# 07_LMS7002M_Power.net
KiCad netlist of a schematic drawn in Altium Designer
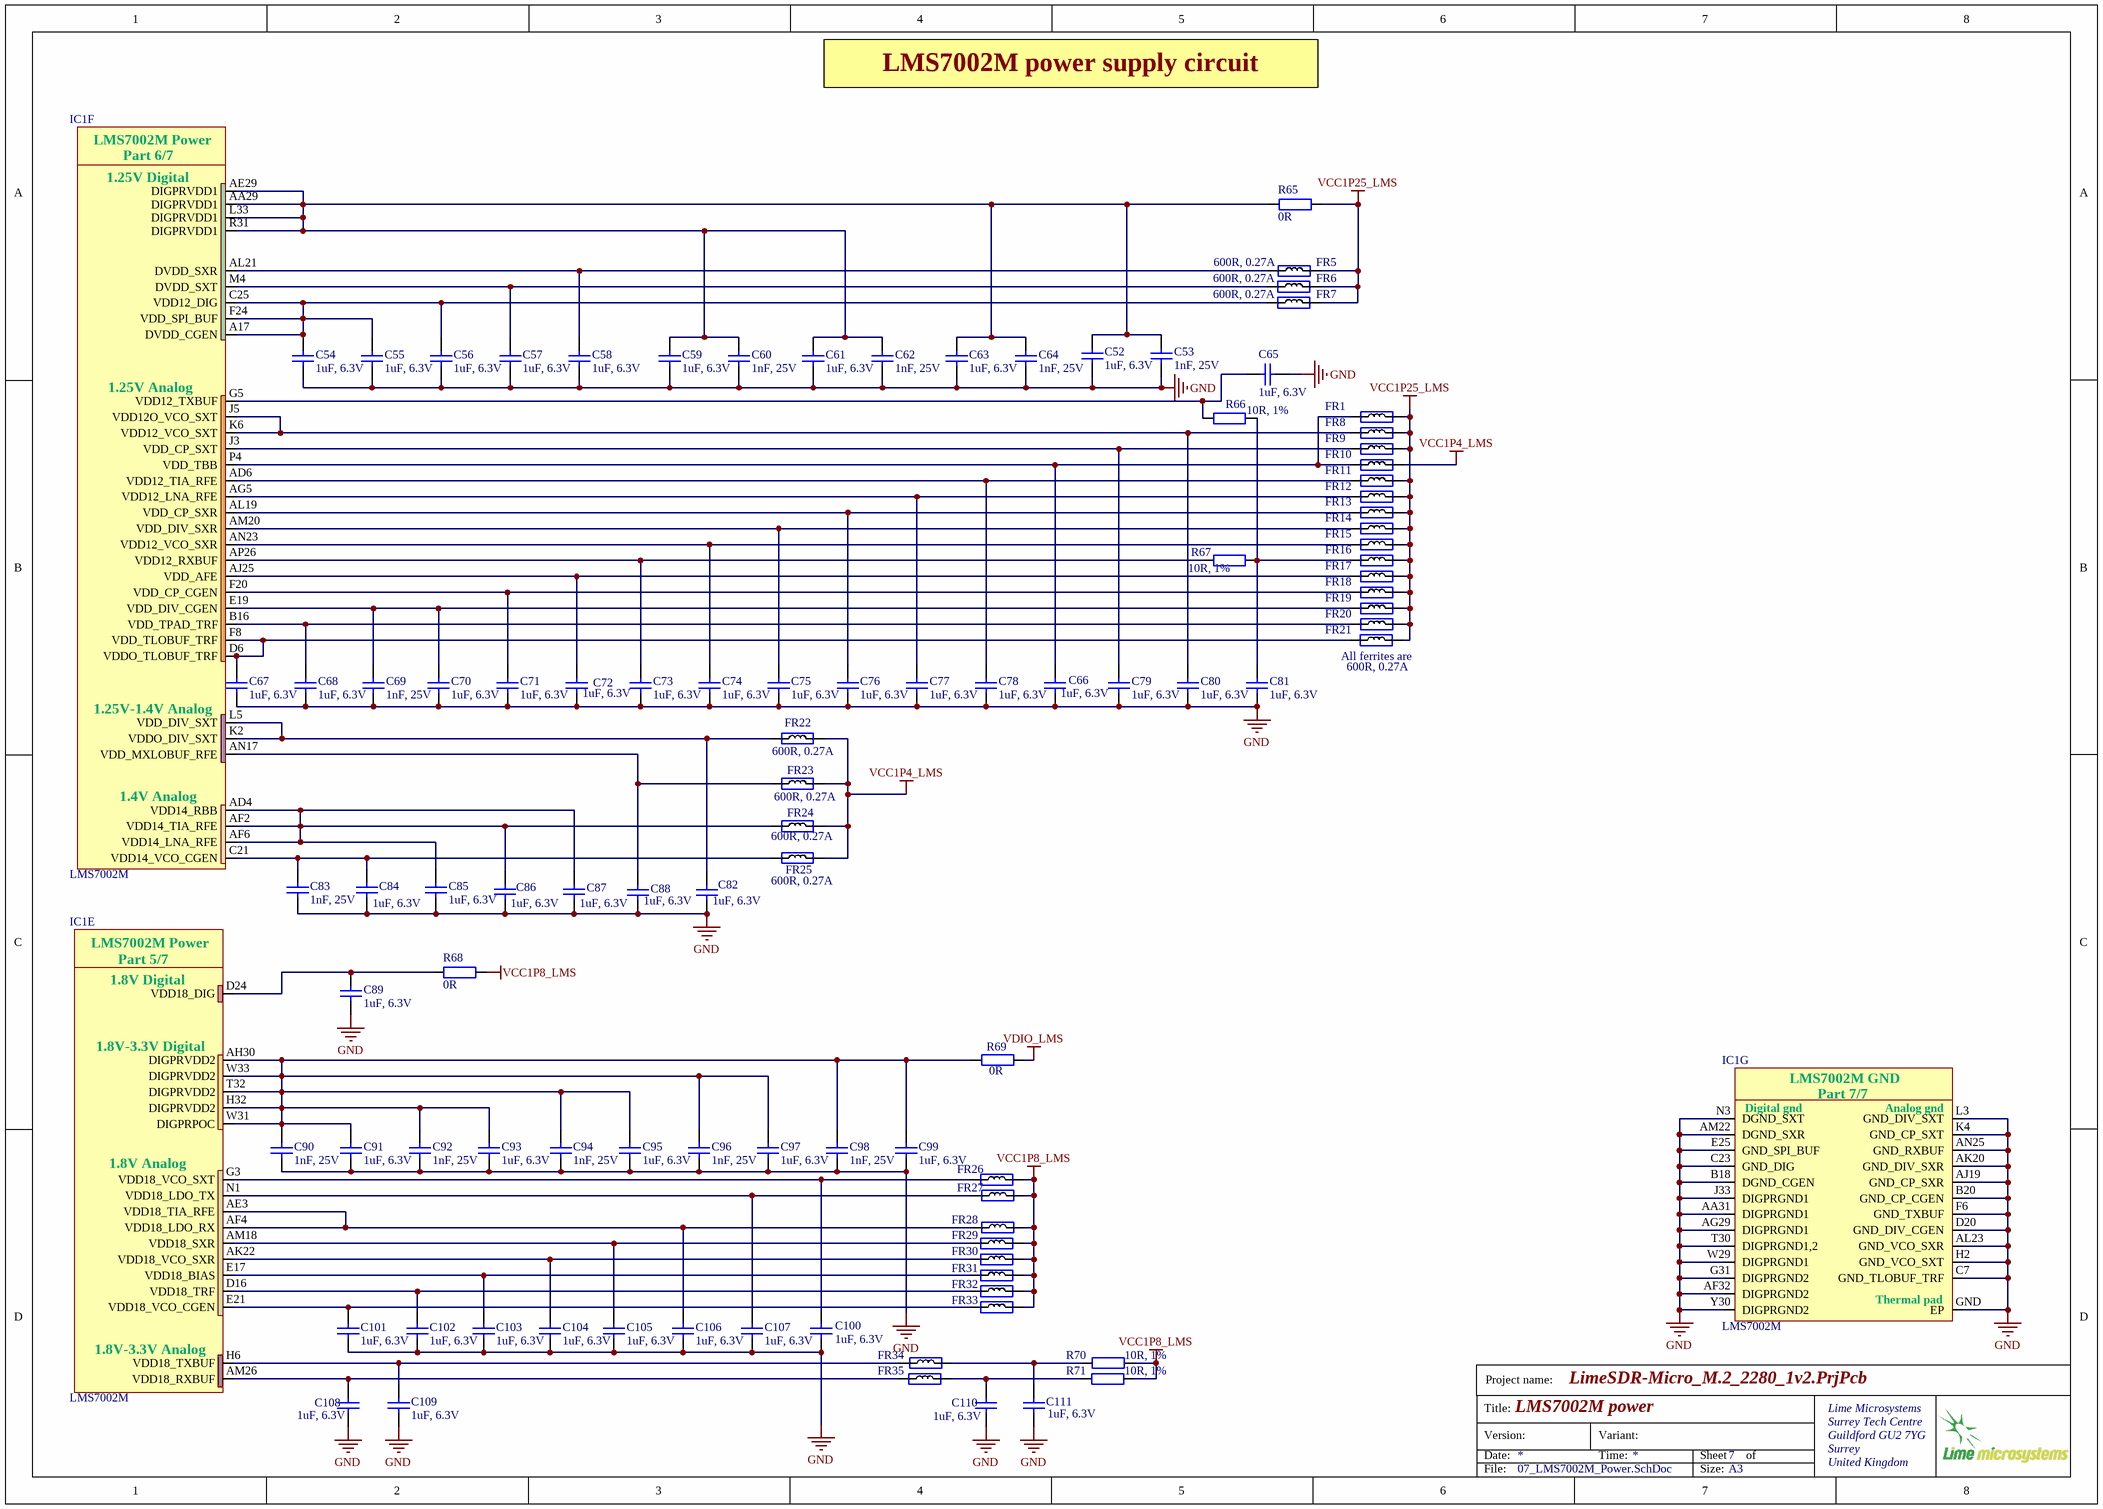
[diagram p0: 07_LMS7002M_Power.SchDoc]

(export (version "E")
  (design (tool "Eeschema 10.0.6"))
  (components
    (comp (ref "C52")
      (value "1uF, 6.3V")
      (footprint "CAP0201")
      (fields (field (name "TOLERANCE") "±20%") (field (name "MANUFACTURER") "TDK Corporation"))
      (libsource (lib "LimeMicroAltiumLib_schLib") (part "Cap_0402"))
    )
    (comp (ref "C53")
      (value "1nF, 25V")
      (footprint "CAP0201")
      (fields (field (name "TOLERANCE") "±10%") (field (name "MANUFACTURER") "TDK Corporation"))
      (libsource (lib "LimeMicroAltiumLib_schLib") (part "Cap_0402"))
    )
    (comp (ref "C54")
      (value "1uF, 6.3V")
      (footprint "CAP0201")
      (fields (field (name "TOLERANCE") "±20%") (field (name "MANUFACTURER") "TDK Corporation"))
      (libsource (lib "LimeMicroAltiumLib_schLib") (part "Cap_0402"))
    )
    (comp (ref "C55")
      (value "1uF, 6.3V")
      (footprint "CAP0201")
      (fields (field (name "TOLERANCE") "±20%") (field (name "MANUFACTURER") "TDK Corporation"))
      (libsource (lib "LimeMicroAltiumLib_schLib") (part "Cap_0402"))
    )
    (comp (ref "C56")
      (value "1uF, 6.3V")
      (footprint "CAP0201")
      (fields (field (name "TOLERANCE") "±20%") (field (name "MANUFACTURER") "TDK Corporation"))
      (libsource (lib "LimeMicroAltiumLib_schLib") (part "Cap_0402"))
    )
    (comp (ref "C57")
      (value "1uF, 6.3V")
      (footprint "CAP0201")
      (fields (field (name "TOLERANCE") "±20%") (field (name "MANUFACTURER") "TDK Corporation"))
      (libsource (lib "LimeMicroAltiumLib_schLib") (part "Cap_0402"))
    )
    (comp (ref "C58")
      (value "1uF, 6.3V")
      (footprint "CAP0201")
      (fields (field (name "TOLERANCE") "±20%") (field (name "MANUFACTURER") "TDK Corporation"))
      (libsource (lib "LimeMicroAltiumLib_schLib") (part "Cap_0402"))
    )
    (comp (ref "C59")
      (value "1uF, 6.3V")
      (footprint "CAP0201")
      (fields (field (name "TOLERANCE") "±20%") (field (name "MANUFACTURER") "TDK Corporation"))
      (libsource (lib "LimeMicroAltiumLib_schLib") (part "Cap_0402"))
    )
    (comp (ref "C60")
      (value "1nF, 25V")
      (footprint "CAP0201")
      (fields (field (name "TOLERANCE") "±10%") (field (name "MANUFACTURER") "TDK Corporation"))
      (libsource (lib "LimeMicroAltiumLib_schLib") (part "Cap_0402"))
    )
    (comp (ref "C61")
      (value "1uF, 6.3V")
      (footprint "CAP0201")
      (fields (field (name "TOLERANCE") "±20%") (field (name "MANUFACTURER") "TDK Corporation"))
      (libsource (lib "LimeMicroAltiumLib_schLib") (part "Cap_0402"))
    )
    (comp (ref "C62")
      (value "1nF, 25V")
      (footprint "CAP0201")
      (fields (field (name "TOLERANCE") "±10%") (field (name "MANUFACTURER") "TDK Corporation"))
      (libsource (lib "LimeMicroAltiumLib_schLib") (part "Cap_0402"))
    )
    (comp (ref "C63")
      (value "1uF, 6.3V")
      (footprint "CAP0201")
      (fields (field (name "TOLERANCE") "±20%") (field (name "MANUFACTURER") "TDK Corporation"))
      (libsource (lib "LimeMicroAltiumLib_schLib") (part "Cap_0402"))
    )
    (comp (ref "C64")
      (value "1nF, 25V")
      (footprint "CAP0201")
      (fields (field (name "TOLERANCE") "±10%") (field (name "MANUFACTURER") "TDK Corporation"))
      (libsource (lib "LimeMicroAltiumLib_schLib") (part "Cap_0402"))
    )
    (comp (ref "C65")
      (value "1uF, 6.3V")
      (footprint "CAP0201")
      (fields (field (name "TOLERANCE") "±20%") (field (name "MANUFACTURER") "TDK Corporation"))
      (libsource (lib "LimeMicroAltiumLib_schLib") (part "Cap_0402"))
    )
    (comp (ref "C66")
      (value "1uF, 6.3V")
      (footprint "CAP0201")
      (fields (field (name "TOLERANCE") "±20%") (field (name "MANUFACTURER") "TDK Corporation"))
      (libsource (lib "LimeMicroAltiumLib_schLib") (part "Cap_0402"))
    )
    (comp (ref "C67")
      (value "1uF, 6.3V")
      (footprint "CAP0201")
      (fields (field (name "TOLERANCE") "±20%") (field (name "MANUFACTURER") "TDK Corporation"))
      (libsource (lib "LimeMicroAltiumLib_schLib") (part "Cap_0402"))
    )
    (comp (ref "C68")
      (value "1uF, 6.3V")
      (footprint "CAP0201")
      (fields (field (name "TOLERANCE") "±20%") (field (name "MANUFACTURER") "TDK Corporation"))
      (libsource (lib "LimeMicroAltiumLib_schLib") (part "Cap_0402"))
    )
    (comp (ref "C69")
      (value "1nF, 25V")
      (footprint "CAP0201")
      (fields (field (name "TOLERANCE") "±10%") (field (name "MANUFACTURER") "TDK Corporation"))
      (libsource (lib "LimeMicroAltiumLib_schLib") (part "Cap_0402"))
    )
    (comp (ref "C70")
      (value "1uF, 6.3V")
      (footprint "CAP0201")
      (fields (field (name "TOLERANCE") "±20%") (field (name "MANUFACTURER") "TDK Corporation"))
      (libsource (lib "LimeMicroAltiumLib_schLib") (part "Cap_0402"))
    )
    (comp (ref "C71")
      (value "1uF, 6.3V")
      (footprint "CAP0201")
      (fields (field (name "TOLERANCE") "±20%") (field (name "MANUFACTURER") "TDK Corporation"))
      (libsource (lib "LimeMicroAltiumLib_schLib") (part "Cap_0402"))
    )
    (comp (ref "C72")
      (value "1uF, 6.3V")
      (footprint "CAP0201")
      (fields (field (name "TOLERANCE") "±20%") (field (name "MANUFACTURER") "TDK Corporation"))
      (libsource (lib "LimeMicroAltiumLib_schLib") (part "Cap_0402"))
    )
    (comp (ref "C73")
      (value "1uF, 6.3V")
      (footprint "CAP0201")
      (fields (field (name "TOLERANCE") "±20%") (field (name "MANUFACTURER") "TDK Corporation"))
      (libsource (lib "LimeMicroAltiumLib_schLib") (part "Cap_0402"))
    )
    (comp (ref "C74")
      (value "1uF, 6.3V")
      (footprint "CAP0201")
      (fields (field (name "TOLERANCE") "±20%") (field (name "MANUFACTURER") "TDK Corporation"))
      (libsource (lib "LimeMicroAltiumLib_schLib") (part "Cap_0402"))
    )
    (comp (ref "C75")
      (value "1uF, 6.3V")
      (footprint "CAP0201")
      (fields (field (name "TOLERANCE") "±20%") (field (name "MANUFACTURER") "TDK Corporation"))
      (libsource (lib "LimeMicroAltiumLib_schLib") (part "Cap_0402"))
    )
    (comp (ref "C76")
      (value "1uF, 6.3V")
      (footprint "CAP0201")
      (fields (field (name "TOLERANCE") "±20%") (field (name "MANUFACTURER") "TDK Corporation"))
      (libsource (lib "LimeMicroAltiumLib_schLib") (part "Cap_0402"))
    )
    (comp (ref "C77")
      (value "1uF, 6.3V")
      (footprint "CAP0201")
      (fields (field (name "TOLERANCE") "±20%") (field (name "MANUFACTURER") "TDK Corporation"))
      (libsource (lib "LimeMicroAltiumLib_schLib") (part "Cap_0402"))
    )
    (comp (ref "C78")
      (value "1uF, 6.3V")
      (footprint "CAP0201")
      (fields (field (name "TOLERANCE") "±20%") (field (name "MANUFACTURER") "TDK Corporation"))
      (libsource (lib "LimeMicroAltiumLib_schLib") (part "Cap_0402"))
    )
    (comp (ref "C79")
      (value "1uF, 6.3V")
      (footprint "CAP0201")
      (fields (field (name "TOLERANCE") "±20%") (field (name "MANUFACTURER") "TDK Corporation"))
      (libsource (lib "LimeMicroAltiumLib_schLib") (part "Cap_0402"))
    )
    (comp (ref "C80")
      (value "1uF, 6.3V")
      (footprint "CAP0201")
      (fields (field (name "TOLERANCE") "±20%") (field (name "MANUFACTURER") "TDK Corporation"))
      (libsource (lib "LimeMicroAltiumLib_schLib") (part "Cap_0402"))
    )
    (comp (ref "C81")
      (value "1uF, 6.3V")
      (footprint "CAP0201")
      (fields (field (name "TOLERANCE") "±20%") (field (name "MANUFACTURER") "TDK Corporation"))
      (libsource (lib "LimeMicroAltiumLib_schLib") (part "Cap_0402"))
    )
    (comp (ref "C82")
      (value "1uF, 6.3V")
      (footprint "CAP0201")
      (fields (field (name "TOLERANCE") "±20%") (field (name "MANUFACTURER") "TDK Corporation"))
      (libsource (lib "LimeMicroAltiumLib_schLib") (part "Cap_0402"))
    )
    (comp (ref "C83")
      (value "1nF, 25V")
      (footprint "CAP0201")
      (fields (field (name "TOLERANCE") "±10%") (field (name "MANUFACTURER") "TDK Corporation"))
      (libsource (lib "LimeMicroAltiumLib_schLib") (part "Cap_0402"))
    )
    (comp (ref "C84")
      (value "1uF, 6.3V")
      (footprint "CAP0201")
      (fields (field (name "TOLERANCE") "±20%") (field (name "MANUFACTURER") "TDK Corporation"))
      (libsource (lib "LimeMicroAltiumLib_schLib") (part "Cap_0402"))
    )
    (comp (ref "C85")
      (value "1uF, 6.3V")
      (footprint "CAP0201")
      (fields (field (name "TOLERANCE") "±20%") (field (name "MANUFACTURER") "TDK Corporation"))
      (libsource (lib "LimeMicroAltiumLib_schLib") (part "Cap_0402"))
    )
    (comp (ref "C86")
      (value "1uF, 6.3V")
      (footprint "CAP0201")
      (fields (field (name "TOLERANCE") "±20%") (field (name "MANUFACTURER") "TDK Corporation"))
      (libsource (lib "LimeMicroAltiumLib_schLib") (part "Cap_0402"))
    )
    (comp (ref "C87")
      (value "1uF, 6.3V")
      (footprint "CAP0201")
      (fields (field (name "TOLERANCE") "±20%") (field (name "MANUFACTURER") "TDK Corporation"))
      (libsource (lib "LimeMicroAltiumLib_schLib") (part "Cap_0402"))
    )
    (comp (ref "C88")
      (value "1uF, 6.3V")
      (footprint "CAP0201")
      (fields (field (name "TOLERANCE") "±20%") (field (name "MANUFACTURER") "TDK Corporation"))
      (libsource (lib "LimeMicroAltiumLib_schLib") (part "Cap_0402"))
    )
    (comp (ref "C89")
      (value "1uF, 6.3V")
      (footprint "CAP0201")
      (fields (field (name "TOLERANCE") "±20%") (field (name "MANUFACTURER") "TDK Corporation"))
      (libsource (lib "LimeMicroAltiumLib_schLib") (part "Cap_0402"))
    )
    (comp (ref "C90")
      (value "1nF, 25V")
      (footprint "CAP0201")
      (fields (field (name "TOLERANCE") "±10%") (field (name "MANUFACTURER") "TDK Corporation"))
      (libsource (lib "LimeMicroAltiumLib_schLib") (part "Cap_0402"))
    )
    (comp (ref "C91")
      (value "1uF, 6.3V")
      (footprint "CAP0201")
      (fields (field (name "TOLERANCE") "±20%") (field (name "MANUFACTURER") "TDK Corporation"))
      (libsource (lib "LimeMicroAltiumLib_schLib") (part "Cap_0402"))
    )
    (comp (ref "C92")
      (value "1nF, 25V")
      (footprint "CAP0201")
      (fields (field (name "TOLERANCE") "±10%") (field (name "MANUFACTURER") "TDK Corporation"))
      (libsource (lib "LimeMicroAltiumLib_schLib") (part "Cap_0402"))
    )
    (comp (ref "C93")
      (value "1uF, 6.3V")
      (footprint "CAP0201")
      (fields (field (name "TOLERANCE") "±20%") (field (name "MANUFACTURER") "TDK Corporation"))
      (libsource (lib "LimeMicroAltiumLib_schLib") (part "Cap_0402"))
    )
    (comp (ref "C94")
      (value "1nF, 25V")
      (footprint "CAP0201")
      (fields (field (name "TOLERANCE") "±10%") (field (name "MANUFACTURER") "TDK Corporation"))
      (libsource (lib "LimeMicroAltiumLib_schLib") (part "Cap_0402"))
    )
    (comp (ref "C95")
      (value "1uF, 6.3V")
      (footprint "CAP0201")
      (fields (field (name "TOLERANCE") "±20%") (field (name "MANUFACTURER") "TDK Corporation"))
      (libsource (lib "LimeMicroAltiumLib_schLib") (part "Cap_0402"))
    )
    (comp (ref "C96")
      (value "1nF, 25V")
      (footprint "CAP0201")
      (fields (field (name "TOLERANCE") "±10%") (field (name "MANUFACTURER") "TDK Corporation"))
      (libsource (lib "LimeMicroAltiumLib_schLib") (part "Cap_0402"))
    )
    (comp (ref "C97")
      (value "1uF, 6.3V")
      (footprint "CAP0201")
      (fields (field (name "TOLERANCE") "±20%") (field (name "MANUFACTURER") "TDK Corporation"))
      (libsource (lib "LimeMicroAltiumLib_schLib") (part "Cap_0402"))
    )
    (comp (ref "C98")
      (value "1nF, 25V")
      (footprint "CAP0201")
      (fields (field (name "TOLERANCE") "±10%") (field (name "MANUFACTURER") "TDK Corporation"))
      (libsource (lib "LimeMicroAltiumLib_schLib") (part "Cap_0402"))
    )
    (comp (ref "C99")
      (value "1uF, 6.3V")
      (footprint "CAP0201")
      (fields (field (name "TOLERANCE") "±20%") (field (name "MANUFACTURER") "TDK Corporation"))
      (libsource (lib "LimeMicroAltiumLib_schLib") (part "Cap_0402"))
    )
    (comp (ref "C100")
      (value "1uF, 6.3V")
      (footprint "CAP0201")
      (fields (field (name "TOLERANCE") "±20%") (field (name "MANUFACTURER") "TDK Corporation"))
      (libsource (lib "LimeMicroAltiumLib_schLib") (part "Cap_0402"))
    )
    (comp (ref "C101")
      (value "1uF, 6.3V")
      (footprint "CAP0201")
      (fields (field (name "TOLERANCE") "±20%") (field (name "MANUFACTURER") "TDK Corporation"))
      (libsource (lib "LimeMicroAltiumLib_schLib") (part "Cap_0402"))
    )
    (comp (ref "C102")
      (value "1uF, 6.3V")
      (footprint "CAP0201")
      (fields (field (name "TOLERANCE") "±20%") (field (name "MANUFACTURER") "TDK Corporation"))
      (libsource (lib "LimeMicroAltiumLib_schLib") (part "Cap_0402"))
    )
    (comp (ref "C103")
      (value "1uF, 6.3V")
      (footprint "CAP0201")
      (fields (field (name "TOLERANCE") "±20%") (field (name "MANUFACTURER") "TDK Corporation"))
      (libsource (lib "LimeMicroAltiumLib_schLib") (part "Cap_0402"))
    )
    (comp (ref "C104")
      (value "1uF, 6.3V")
      (footprint "CAP0201")
      (fields (field (name "TOLERANCE") "±20%") (field (name "MANUFACTURER") "TDK Corporation"))
      (libsource (lib "LimeMicroAltiumLib_schLib") (part "Cap_0402"))
    )
    (comp (ref "C105")
      (value "1uF, 6.3V")
      (footprint "CAP0201")
      (fields (field (name "TOLERANCE") "±20%") (field (name "MANUFACTURER") "TDK Corporation"))
      (libsource (lib "LimeMicroAltiumLib_schLib") (part "Cap_0402"))
    )
    (comp (ref "C106")
      (value "1uF, 6.3V")
      (footprint "CAP0201")
      (fields (field (name "TOLERANCE") "±20%") (field (name "MANUFACTURER") "TDK Corporation"))
      (libsource (lib "LimeMicroAltiumLib_schLib") (part "Cap_0402"))
    )
    (comp (ref "C107")
      (value "1uF, 6.3V")
      (footprint "CAP0201")
      (fields (field (name "TOLERANCE") "±20%") (field (name "MANUFACTURER") "TDK Corporation"))
      (libsource (lib "LimeMicroAltiumLib_schLib") (part "Cap_0402"))
    )
    (comp (ref "C108")
      (value "1uF, 6.3V")
      (footprint "CAP0201")
      (fields (field (name "TOLERANCE") "±20%") (field (name "MANUFACTURER") "TDK Corporation"))
      (libsource (lib "LimeMicroAltiumLib_schLib") (part "Cap_0402"))
    )
    (comp (ref "C109")
      (value "1uF, 6.3V")
      (footprint "CAP0201")
      (fields (field (name "TOLERANCE") "±20%") (field (name "MANUFACTURER") "TDK Corporation"))
      (libsource (lib "LimeMicroAltiumLib_schLib") (part "Cap_0402"))
    )
    (comp (ref "C110")
      (value "1uF, 6.3V")
      (footprint "CAP0201")
      (fields (field (name "TOLERANCE") "±20%") (field (name "MANUFACTURER") "TDK Corporation"))
      (libsource (lib "LimeMicroAltiumLib_schLib") (part "Cap_0402"))
    )
    (comp (ref "C111")
      (value "1uF, 6.3V")
      (footprint "CAP0201")
      (fields (field (name "TOLERANCE") "±20%") (field (name "MANUFACTURER") "TDK Corporation"))
      (libsource (lib "LimeMicroAltiumLib_schLib") (part "Cap_0402"))
    )
    (comp (ref "FR1")
      (value "600R, 0.27A")
      (footprint "RES0201")
      (fields (field (name "MANUFACTURER") "Taiyo Yuden"))
      (libsource (lib "LimeMicroAltiumLib_schLib") (part "Ferrite"))
    )
    (comp (ref "FR5")
      (value "600R, 0.27A")
      (footprint "RES0201")
      (fields (field (name "MANUFACTURER") "Taiyo Yuden"))
      (libsource (lib "LimeMicroAltiumLib_schLib") (part "Ferrite"))
    )
    (comp (ref "FR6")
      (value "600R, 0.27A")
      (footprint "RES0201")
      (fields (field (name "MANUFACTURER") "Taiyo Yuden"))
      (libsource (lib "LimeMicroAltiumLib_schLib") (part "Ferrite"))
    )
    (comp (ref "FR7")
      (value "600R, 0.27A")
      (footprint "RES0201")
      (fields (field (name "MANUFACTURER") "Taiyo Yuden"))
      (libsource (lib "LimeMicroAltiumLib_schLib") (part "Ferrite"))
    )
    (comp (ref "FR8")
      (value "600R, 0.27A")
      (footprint "RES0201")
      (fields (field (name "MANUFACTURER") "Taiyo Yuden"))
      (libsource (lib "LimeMicroAltiumLib_schLib") (part "Ferrite"))
    )
    (comp (ref "FR9")
      (value "600R, 0.27A")
      (footprint "RES0201")
      (fields (field (name "MANUFACTURER") "Taiyo Yuden"))
      (libsource (lib "LimeMicroAltiumLib_schLib") (part "Ferrite"))
    )
    (comp (ref "FR10")
      (value "600R, 0.27A")
      (footprint "RES0201")
      (fields (field (name "MANUFACTURER") "Taiyo Yuden"))
      (libsource (lib "LimeMicroAltiumLib_schLib") (part "Ferrite"))
    )
    (comp (ref "FR11")
      (value "600R, 0.27A")
      (footprint "RES0201")
      (fields (field (name "MANUFACTURER") "Taiyo Yuden"))
      (libsource (lib "LimeMicroAltiumLib_schLib") (part "Ferrite"))
    )
    (comp (ref "FR12")
      (value "600R, 0.27A")
      (footprint "RES0201")
      (fields (field (name "MANUFACTURER") "Taiyo Yuden"))
      (libsource (lib "LimeMicroAltiumLib_schLib") (part "Ferrite"))
    )
    (comp (ref "FR13")
      (value "600R, 0.27A")
      (footprint "RES0201")
      (fields (field (name "MANUFACTURER") "Taiyo Yuden"))
      (libsource (lib "LimeMicroAltiumLib_schLib") (part "Ferrite"))
    )
    (comp (ref "FR14")
      (value "600R, 0.27A")
      (footprint "RES0201")
      (fields (field (name "MANUFACTURER") "Taiyo Yuden"))
      (libsource (lib "LimeMicroAltiumLib_schLib") (part "Ferrite"))
    )
    (comp (ref "FR15")
      (value "600R, 0.27A")
      (footprint "RES0201")
      (fields (field (name "MANUFACTURER") "Taiyo Yuden"))
      (libsource (lib "LimeMicroAltiumLib_schLib") (part "Ferrite"))
    )
    (comp (ref "FR16")
      (value "600R, 0.27A")
      (footprint "RES0201")
      (fields (field (name "MANUFACTURER") "Taiyo Yuden"))
      (libsource (lib "LimeMicroAltiumLib_schLib") (part "Ferrite"))
    )
    (comp (ref "FR17")
      (value "600R, 0.27A")
      (footprint "RES0201")
      (fields (field (name "MANUFACTURER") "Taiyo Yuden"))
      (libsource (lib "LimeMicroAltiumLib_schLib") (part "Ferrite"))
    )
    (comp (ref "FR18")
      (value "600R, 0.27A")
      (footprint "RES0201")
      (fields (field (name "MANUFACTURER") "Taiyo Yuden"))
      (libsource (lib "LimeMicroAltiumLib_schLib") (part "Ferrite"))
    )
    (comp (ref "FR19")
      (value "600R, 0.27A")
      (footprint "RES0201")
      (fields (field (name "MANUFACTURER") "Taiyo Yuden"))
      (libsource (lib "LimeMicroAltiumLib_schLib") (part "Ferrite"))
    )
    (comp (ref "FR20")
      (value "600R, 0.27A")
      (footprint "RES0201")
      (fields (field (name "MANUFACTURER") "Taiyo Yuden"))
      (libsource (lib "LimeMicroAltiumLib_schLib") (part "Ferrite"))
    )
    (comp (ref "FR21")
      (value "600R, 0.27A")
      (footprint "RES0201")
      (fields (field (name "MANUFACTURER") "Taiyo Yuden"))
      (libsource (lib "LimeMicroAltiumLib_schLib") (part "Ferrite"))
    )
    (comp (ref "FR22")
      (value "600R, 0.27A")
      (footprint "RES0201")
      (fields (field (name "MANUFACTURER") "Taiyo Yuden"))
      (libsource (lib "LimeMicroAltiumLib_schLib") (part "Ferrite"))
    )
    (comp (ref "FR23")
      (value "600R, 0.27A")
      (footprint "RES0201")
      (fields (field (name "MANUFACTURER") "Taiyo Yuden"))
      (libsource (lib "LimeMicroAltiumLib_schLib") (part "Ferrite"))
    )
    (comp (ref "FR24")
      (value "600R, 0.27A")
      (footprint "RES0201")
      (fields (field (name "MANUFACTURER") "Taiyo Yuden"))
      (libsource (lib "LimeMicroAltiumLib_schLib") (part "Ferrite"))
    )
    (comp (ref "FR25")
      (value "600R, 0.27A")
      (footprint "RES0201")
      (fields (field (name "MANUFACTURER") "Taiyo Yuden"))
      (libsource (lib "LimeMicroAltiumLib_schLib") (part "Ferrite"))
    )
    (comp (ref "FR26")
      (value "600R, 0.27A")
      (footprint "RES0201")
      (fields (field (name "MANUFACTURER") "Taiyo Yuden"))
      (libsource (lib "LimeMicroAltiumLib_schLib") (part "Ferrite"))
    )
    (comp (ref "FR27")
      (value "600R, 0.27A")
      (footprint "RES0201")
      (fields (field (name "MANUFACTURER") "Taiyo Yuden"))
      (libsource (lib "") (part "Ferrite_1"))
    )
    (comp (ref "FR28")
      (value "600R, 0.27A")
      (footprint "RES0201")
      (fields (field (name "MANUFACTURER") "Taiyo Yuden"))
      (libsource (lib "") (part "Ferrite_1"))
    )
    (comp (ref "FR29")
      (value "600R, 0.27A")
      (footprint "RES0201")
      (fields (field (name "MANUFACTURER") "Taiyo Yuden"))
      (libsource (lib "LimeMicroAltiumLib_schLib") (part "Ferrite"))
    )
    (comp (ref "FR30")
      (value "600R, 0.27A")
      (footprint "RES0201")
      (fields (field (name "MANUFACTURER") "Taiyo Yuden"))
      (libsource (lib "LimeMicroAltiumLib_schLib") (part "Ferrite"))
    )
    (comp (ref "FR31")
      (value "600R, 0.27A")
      (footprint "RES0201")
      (fields (field (name "MANUFACTURER") "Taiyo Yuden"))
      (libsource (lib "LimeMicroAltiumLib_schLib") (part "Ferrite"))
    )
    (comp (ref "FR32")
      (value "600R, 0.27A")
      (footprint "RES0201")
      (fields (field (name "MANUFACTURER") "Taiyo Yuden"))
      (libsource (lib "LimeMicroAltiumLib_schLib") (part "Ferrite"))
    )
    (comp (ref "FR33")
      (value "600R, 0.27A")
      (footprint "RES0201")
      (fields (field (name "MANUFACTURER") "Taiyo Yuden"))
      (libsource (lib "LimeMicroAltiumLib_schLib") (part "Ferrite"))
    )
    (comp (ref "FR34")
      (value "600R, 0.27A")
      (footprint "RES0201")
      (fields (field (name "MANUFACTURER") "Taiyo Yuden"))
      (libsource (lib "") (part "Ferrite_1"))
    )
    (comp (ref "FR35")
      (value "600R, 0.27A")
      (footprint "RES0201")
      (fields (field (name "MANUFACTURER") "Taiyo Yuden"))
      (libsource (lib "LimeMicroAltiumLib_schLib") (part "Ferrite"))
    )
    (comp (ref "IC1")
      (value "LMS7002M")
      (footprint "LMS7002M_v5_LESS_SILK")
      (description "Schematic symbol revision 4. Default footprint - 0.31mm pad")
      (fields (field (name "MANUFACTURER") "Lime Microsystems"))
      (libsource (lib "LimeMicroAltiumLib_schLib_r04") (part "LMS7002Mr4"))
    )
    (comp (ref "R65")
      (value "0R")
      (footprint "RES0402")
      (fields (field (name "MANUFACTURER") "Yageo") (field (name "TOLERANCE") "Jumper"))
      (libsource (lib "LimeMicroAltiumLib_schLib") (part "Res_0402"))
    )
    (comp (ref "R66")
      (value "10R, 1%")
      (footprint "RES0201")
      (fields
        (field (name "MANUFACTURER") "Panasonic Electronic Components")
        (field (name "TOLERANCE") "±1%")
      )
      (libsource (lib "LimeMicroAltiumLib_schLib") (part "Res_0402"))
    )
    (comp (ref "R67")
      (value "10R, 1%")
      (footprint "RES0201")
      (fields
        (field (name "MANUFACTURER") "Panasonic Electronic Components")
        (field (name "TOLERANCE") "±1%")
      )
      (libsource (lib "LimeMicroAltiumLib_schLib") (part "Res_0402"))
    )
    (comp (ref "R68")
      (value "0R")
      (footprint "RES0201")
      (fields (field (name "MANUFACTURER") "Yageo") (field (name "TOLERANCE") "5%"))
      (libsource (lib "LimeMicroAltiumLib_schLib") (part "Res_0402"))
    )
    (comp (ref "R69")
      (value "0R")
      (footprint "RES0402")
      (fields (field (name "MANUFACTURER") "Yageo") (field (name "TOLERANCE") "Jumper"))
      (libsource (lib "LimeMicroAltiumLib_schLib") (part "Res_0402"))
    )
    (comp (ref "R70")
      (value "10R, 1%")
      (footprint "RES0201")
      (fields
        (field (name "MANUFACTURER") "Panasonic Electronic Components")
        (field (name "TOLERANCE") "±1%")
      )
      (libsource (lib "LimeMicroAltiumLib_schLib") (part "Res_0402"))
    )
    (comp (ref "R71")
      (value "10R, 1%")
      (footprint "RES0201")
      (fields
        (field (name "MANUFACTURER") "Panasonic Electronic Components")
        (field (name "TOLERANCE") "±1%")
      )
      (libsource (lib "LimeMicroAltiumLib_schLib") (part "Res_0402"))
    )
  )
  (nets
    (net (code "1") (name "GND") (class "Default")
      (node (ref "C100") (pin "2") (pinfunction "2_2") (pintype "passive"))
      (node (ref "C101") (pin "2") (pinfunction "2_2") (pintype "passive"))
      (node (ref "C102") (pin "2") (pinfunction "2_2") (pintype "passive"))
      (node (ref "C103") (pin "2") (pinfunction "2_2") (pintype "passive"))
      (node (ref "C104") (pin "2") (pinfunction "2_2") (pintype "passive"))
      (node (ref "C105") (pin "2") (pinfunction "2_2") (pintype "passive"))
      (node (ref "C106") (pin "2") (pinfunction "2_2") (pintype "passive"))
      (node (ref "C107") (pin "2") (pinfunction "2_2") (pintype "passive"))
      (node (ref "C108") (pin "2") (pinfunction "2_2") (pintype "passive"))
      (node (ref "C109") (pin "2") (pinfunction "2_2") (pintype "passive"))
      (node (ref "C110") (pin "2") (pinfunction "2_2") (pintype "passive"))
      (node (ref "C111") (pin "2") (pinfunction "2_2") (pintype "passive"))
      (node (ref "C52") (pin "2") (pinfunction "2_2") (pintype "passive"))
      (node (ref "C53") (pin "2") (pinfunction "2_2") (pintype "passive"))
      (node (ref "C54") (pin "2") (pinfunction "2_2") (pintype "passive"))
      (node (ref "C55") (pin "2") (pinfunction "2_2") (pintype "passive"))
      (node (ref "C56") (pin "2") (pinfunction "2_2") (pintype "passive"))
      (node (ref "C57") (pin "1") (pinfunction "1_1") (pintype "passive"))
      (node (ref "C58") (pin "2") (pinfunction "2_2") (pintype "passive"))
      (node (ref "C59") (pin "2") (pinfunction "2_2") (pintype "passive"))
      (node (ref "C60") (pin "2") (pinfunction "2_2") (pintype "passive"))
      (node (ref "C61") (pin "2") (pinfunction "2_2") (pintype "passive"))
      (node (ref "C62") (pin "2") (pinfunction "2_2") (pintype "passive"))
      (node (ref "C63") (pin "2") (pinfunction "2_2") (pintype "passive"))
      (node (ref "C64") (pin "2") (pinfunction "2_2") (pintype "passive"))
      (node (ref "C65") (pin "2") (pinfunction "2_2") (pintype "passive"))
      (node (ref "C66") (pin "2") (pinfunction "2_2") (pintype "passive"))
      (node (ref "C67") (pin "2") (pinfunction "2_2") (pintype "passive"))
      (node (ref "C68") (pin "2") (pinfunction "2_2") (pintype "passive"))
      (node (ref "C69") (pin "2") (pinfunction "2_2") (pintype "passive"))
      (node (ref "C70") (pin "2") (pinfunction "2_2") (pintype "passive"))
      (node (ref "C71") (pin "1") (pinfunction "1_1") (pintype "passive"))
      (node (ref "C72") (pin "2") (pinfunction "2_2") (pintype "passive"))
      (node (ref "C73") (pin "2") (pinfunction "2_2") (pintype "passive"))
      (node (ref "C74") (pin "2") (pinfunction "2_2") (pintype "passive"))
      (node (ref "C75") (pin "2") (pinfunction "2_2") (pintype "passive"))
      (node (ref "C76") (pin "2") (pinfunction "2_2") (pintype "passive"))
      (node (ref "C77") (pin "2") (pinfunction "2_2") (pintype "passive"))
      (node (ref "C78") (pin "1") (pinfunction "1_1") (pintype "passive"))
      (node (ref "C79") (pin "2") (pinfunction "2_2") (pintype "passive"))
      (node (ref "C80") (pin "1") (pinfunction "1_1") (pintype "passive"))
      (node (ref "C81") (pin "1") (pinfunction "1_1") (pintype "passive"))
      (node (ref "C82") (pin "2") (pinfunction "2_2") (pintype "passive"))
      (node (ref "C83") (pin "2") (pinfunction "2_2") (pintype "passive"))
      (node (ref "C84") (pin "2") (pinfunction "2_2") (pintype "passive"))
      (node (ref "C85") (pin "2") (pinfunction "2_2") (pintype "passive"))
      (node (ref "C86") (pin "2") (pinfunction "2_2") (pintype "passive"))
      (node (ref "C87") (pin "2") (pinfunction "2_2") (pintype "passive"))
      (node (ref "C88") (pin "2") (pinfunction "2_2") (pintype "passive"))
      (node (ref "C89") (pin "2") (pinfunction "2_2") (pintype "passive"))
      (node (ref "C90") (pin "2") (pinfunction "2_2") (pintype "passive"))
      (node (ref "C91") (pin "2") (pinfunction "2_2") (pintype "passive"))
      (node (ref "C92") (pin "2") (pinfunction "2_2") (pintype "passive"))
      (node (ref "C93") (pin "2") (pinfunction "2_2") (pintype "passive"))
      (node (ref "C94") (pin "2") (pinfunction "2_2") (pintype "passive"))
      (node (ref "C95") (pin "2") (pinfunction "2_2") (pintype "passive"))
      (node (ref "C96") (pin "2") (pinfunction "2_2") (pintype "passive"))
      (node (ref "C97") (pin "2") (pinfunction "2_2") (pintype "passive"))
      (node (ref "C98") (pin "2") (pinfunction "2_2") (pintype "passive"))
      (node (ref "C99") (pin "2") (pinfunction "2_2") (pintype "passive"))
      (node (ref "IC1") (pin "AA31") (pinfunction "DIGPRGND1_AA31") (pintype "passive"))
      (node (ref "IC1") (pin "AF32") (pinfunction "DIGPRGND2_AF32") (pintype "passive"))
      (node (ref "IC1") (pin "AG29") (pinfunction "DIGPRGND1_AG29") (pintype "passive"))
      (node (ref "IC1") (pin "AJ19") (pinfunction "GND_CP_SXR_AJ19") (pintype "passive"))
      (node (ref "IC1") (pin "AK20") (pinfunction "GND_DIV_SXR_AK20") (pintype "passive"))
      (node (ref "IC1") (pin "AL23") (pinfunction "GND_VCO_SXR_AL23") (pintype "passive"))
      (node (ref "IC1") (pin "AM22") (pinfunction "DGND_SXR_AM22") (pintype "passive"))
      (node (ref "IC1") (pin "AN25") (pinfunction "GND_RXBUF_AN25") (pintype "passive"))
      (node (ref "IC1") (pin "B18") (pinfunction "DGND_CGEN_B18") (pintype "passive"))
      (node (ref "IC1") (pin "B20") (pinfunction "GND_CP_CGEN_B20") (pintype "passive"))
      (node (ref "IC1") (pin "C23") (pinfunction "GND_DIG_C23") (pintype "passive"))
      (node (ref "IC1") (pin "C7") (pinfunction "GND_TLOBUF_TRF_C7") (pintype "passive"))
      (node (ref "IC1") (pin "D20") (pinfunction "GND_DIV_CGEN_D20") (pintype "passive"))
      (node (ref "IC1") (pin "E25") (pinfunction "GND_SPI_BUF_E25") (pintype "passive"))
      (node (ref "IC1") (pin "F6") (pinfunction "GND_TXBUF_F6") (pintype "passive"))
      (node (ref "IC1") (pin "G31") (pinfunction "DIGPRGND2_G31") (pintype "passive"))
      (node (ref "IC1") (pin "GND") (pinfunction "EP_GND") (pintype "passive"))
      (node (ref "IC1") (pin "H2") (pinfunction "GND_VCO_SXT_H2") (pintype "passive"))
      (node (ref "IC1") (pin "J33") (pinfunction "DIGPRGND1_J33") (pintype "passive"))
      (node (ref "IC1") (pin "K4") (pinfunction "GND_CP_SXT_K4") (pintype "passive"))
      (node (ref "IC1") (pin "L3") (pinfunction "GND_DIV_SXT_L3") (pintype "passive"))
      (node (ref "IC1") (pin "N3") (pinfunction "DGND_SXT_N3") (pintype "passive"))
      (node (ref "IC1") (pin "T30") (pinfunction "DIGPRGND1,2_T30") (pintype "passive"))
      (node (ref "IC1") (pin "W29") (pinfunction "DIGPRGND1_W29") (pintype "passive"))
      (node (ref "IC1") (pin "Y30") (pinfunction "DIGPRGND2_Y30") (pintype "passive"))
    )
    (net (code "2") (name "Net-(C52-Pad1)") (class "Default")
      (node (ref "C52") (pin "1") (pinfunction "1_1") (pintype "passive"))
      (node (ref "C53") (pin "1") (pinfunction "1_1") (pintype "passive"))
      (node (ref "C59") (pin "1") (pinfunction "1_1") (pintype "passive"))
      (node (ref "C60") (pin "1") (pinfunction "1_1") (pintype "passive"))
      (node (ref "C61") (pin "1") (pinfunction "1_1") (pintype "passive"))
      (node (ref "C62") (pin "1") (pinfunction "1_1") (pintype "passive"))
      (node (ref "C63") (pin "1") (pinfunction "1_1") (pintype "passive"))
      (node (ref "C64") (pin "1") (pinfunction "1_1") (pintype "passive"))
      (node (ref "IC1") (pin "AA29") (pinfunction "DIGPRVDD1_AA29") (pintype "power_in"))
      (node (ref "IC1") (pin "AE29") (pinfunction "DIGPRVDD1_AE29") (pintype "power_in"))
      (node (ref "IC1") (pin "L33") (pinfunction "DIGPRVDD1_L33") (pintype "power_in"))
      (node (ref "IC1") (pin "R31") (pinfunction "DIGPRVDD1_R31") (pintype "power_in"))
      (node (ref "R65") (pin "2") (pinfunction "2_2") (pintype "passive"))
    )
    (net (code "3") (name "Net-(C81-Pad2)") (class "Default")
      (node (ref "C81") (pin "2") (pinfunction "2_2") (pintype "passive"))
      (node (ref "FR16") (pin "1") (pinfunction "1_1") (pintype "passive"))
      (node (ref "R66") (pin "2") (pinfunction "2_2") (pintype "passive"))
      (node (ref "R67") (pin "2") (pinfunction "2_2") (pintype "passive"))
    )
    (net (code "4") (name "Net-(C110-Pad1)") (class "Default")
      (node (ref "C110") (pin "1") (pinfunction "1_1") (pintype "passive"))
      (node (ref "FR35") (pin "2") (pinfunction "2_2") (pintype "passive"))
      (node (ref "R71") (pin "2") (pinfunction "2_2") (pintype "passive"))
    )
    (net (code "5") (name "Net-(C111-Pad1)") (class "Default")
      (node (ref "C111") (pin "1") (pinfunction "1_1") (pintype "passive"))
      (node (ref "FR34") (pin "1") (pinfunction "1_1") (pintype "passive"))
      (node (ref "R70") (pin "1") (pinfunction "1_1") (pintype "passive"))
    )
    (net (code "6") (name "Net-(IC1E-DIGPRPOC)") (class "Default")
      (node (ref "C90") (pin "1") (pinfunction "1_1") (pintype "passive"))
      (node (ref "C91") (pin "1") (pinfunction "1_1") (pintype "passive"))
      (node (ref "C92") (pin "1") (pinfunction "1_1") (pintype "passive"))
      (node (ref "C93") (pin "1") (pinfunction "1_1") (pintype "passive"))
      (node (ref "C94") (pin "1") (pinfunction "1_1") (pintype "passive"))
      (node (ref "C95") (pin "1") (pinfunction "1_1") (pintype "passive"))
      (node (ref "C96") (pin "1") (pinfunction "1_1") (pintype "passive"))
      (node (ref "C97") (pin "1") (pinfunction "1_1") (pintype "passive"))
      (node (ref "C98") (pin "1") (pinfunction "1_1") (pintype "passive"))
      (node (ref "C99") (pin "1") (pinfunction "1_1") (pintype "passive"))
      (node (ref "IC1") (pin "AH30") (pinfunction "DIGPRVDD2_AH30") (pintype "power_in"))
      (node (ref "IC1") (pin "H32") (pinfunction "DIGPRVDD2_H32") (pintype "power_in"))
      (node (ref "IC1") (pin "T32") (pinfunction "DIGPRVDD2_T32") (pintype "power_in"))
      (node (ref "IC1") (pin "W31") (pinfunction "DIGPRPOC_W31") (pintype "power_in"))
      (node (ref "IC1") (pin "W33") (pinfunction "DIGPRVDD2_W33") (pintype "power_in"))
      (node (ref "R69") (pin "2") (pinfunction "2_2") (pintype "passive"))
    )
    (net (code "7") (name "Net-(IC1E-VDD18_BIAS)") (class "Default")
      (node (ref "C103") (pin "1") (pinfunction "1_1") (pintype "passive"))
      (node (ref "FR31") (pin "1") (pinfunction "1_1") (pintype "passive"))
      (node (ref "IC1") (pin "E17") (pinfunction "VDD18_BIAS_E17") (pintype "power_in"))
    )
    (net (code "8") (name "Net-(IC1E-VDD18_DIG)") (class "Default")
      (node (ref "C89") (pin "1") (pinfunction "1_1") (pintype "passive"))
      (node (ref "IC1") (pin "D24") (pinfunction "VDD18_DIG_D24") (pintype "power_in"))
      (node (ref "R68") (pin "1") (pinfunction "1_1") (pintype "passive"))
    )
    (net (code "9") (name "Net-(IC1E-VDD18_LDO_RX)") (class "Default")
      (node (ref "C106") (pin "1") (pinfunction "1_1") (pintype "passive"))
      (node (ref "FR28") (pin "2") (pinfunction "2_2") (pintype "passive"))
      (node (ref "IC1") (pin "AE3") (pinfunction "VDD18_TIA_RFE_AE3") (pintype "power_in"))
      (node (ref "IC1") (pin "AF4") (pinfunction "VDD18_LDO_RX_AF4") (pintype "power_in"))
    )
    (net (code "10") (name "Net-(IC1E-VDD18_LDO_TX)") (class "Default")
      (node (ref "C107") (pin "1") (pinfunction "1_1") (pintype "passive"))
      (node (ref "FR27") (pin "2") (pinfunction "2_2") (pintype "passive"))
      (node (ref "IC1") (pin "N1") (pinfunction "VDD18_LDO_TX_N1") (pintype "power_in"))
    )
    (net (code "11") (name "Net-(IC1E-VDD18_RXBUF)") (class "Default")
      (node (ref "C108") (pin "1") (pinfunction "1_1") (pintype "passive"))
      (node (ref "FR35") (pin "1") (pinfunction "1_1") (pintype "passive"))
      (node (ref "IC1") (pin "AM26") (pinfunction "VDD18_RXBUF_AM26") (pintype "power_in"))
    )
    (net (code "12") (name "Net-(IC1E-VDD18_SXR)") (class "Default")
      (node (ref "C105") (pin "1") (pinfunction "1_1") (pintype "passive"))
      (node (ref "FR29") (pin "1") (pinfunction "1_1") (pintype "passive"))
      (node (ref "IC1") (pin "AM18") (pinfunction "VDD18_SXR_AM18") (pintype "power_in"))
    )
    (net (code "13") (name "Net-(IC1E-VDD18_TRF)") (class "Default")
      (node (ref "C102") (pin "1") (pinfunction "1_1") (pintype "passive"))
      (node (ref "FR32") (pin "1") (pinfunction "1_1") (pintype "passive"))
      (node (ref "IC1") (pin "D16") (pinfunction "VDD18_TRF_D16") (pintype "power_in"))
    )
    (net (code "14") (name "Net-(IC1E-VDD18_TXBUF)") (class "Default")
      (node (ref "C109") (pin "1") (pinfunction "1_1") (pintype "passive"))
      (node (ref "FR34") (pin "2") (pinfunction "2_2") (pintype "passive"))
      (node (ref "IC1") (pin "H6") (pinfunction "VDD18_TXBUF_H6") (pintype "power_in"))
    )
    (net (code "15") (name "Net-(IC1E-VDD18_VCO_CGEN)") (class "Default")
      (node (ref "C101") (pin "1") (pinfunction "1_1") (pintype "passive"))
      (node (ref "FR33") (pin "1") (pinfunction "1_1") (pintype "passive"))
      (node (ref "IC1") (pin "E21") (pinfunction "VDD18_VCO_CGEN_E21") (pintype "power_in"))
    )
    (net (code "16") (name "Net-(IC1E-VDD18_VCO_SXR)") (class "Default")
      (node (ref "C104") (pin "1") (pinfunction "1_1") (pintype "passive"))
      (node (ref "FR30") (pin "1") (pinfunction "1_1") (pintype "passive"))
      (node (ref "IC1") (pin "AK22") (pinfunction "VDD18_VCO_SXR_AK22") (pintype "power_in"))
    )
    (net (code "17") (name "Net-(IC1E-VDD18_VCO_SXT)") (class "Default")
      (node (ref "C100") (pin "1") (pinfunction "1_1") (pintype "passive"))
      (node (ref "FR26") (pin "1") (pinfunction "1_1") (pintype "passive"))
      (node (ref "IC1") (pin "G3") (pinfunction "VDD18_VCO_SXT_G3") (pintype "power_in"))
    )
    (net (code "18") (name "Net-(IC1F-DVDD_CGEN)") (class "Default")
      (node (ref "C54") (pin "1") (pinfunction "1_1") (pintype "passive"))
      (node (ref "C55") (pin "1") (pinfunction "1_1") (pintype "passive"))
      (node (ref "C56") (pin "1") (pinfunction "1_1") (pintype "passive"))
      (node (ref "FR7") (pin "1") (pinfunction "1_1") (pintype "passive"))
      (node (ref "IC1") (pin "A17") (pinfunction "DVDD_CGEN_A17") (pintype "power_in"))
      (node (ref "IC1") (pin "C25") (pinfunction "VDD12_DIG_C25") (pintype "power_in"))
      (node (ref "IC1") (pin "F24") (pinfunction "VDD_SPI_BUF_F24") (pintype "power_in"))
    )
    (net (code "19") (name "Net-(IC1F-DVDD_SXR)") (class "Default")
      (node (ref "C58") (pin "1") (pinfunction "1_1") (pintype "passive"))
      (node (ref "FR5") (pin "1") (pinfunction "1_1") (pintype "passive"))
      (node (ref "IC1") (pin "AL21") (pinfunction "DVDD_SXR_AL21") (pintype "power_in"))
    )
    (net (code "20") (name "Net-(IC1F-DVDD_SXT)") (class "Default")
      (node (ref "C57") (pin "2") (pinfunction "2_2") (pintype "passive"))
      (node (ref "FR6") (pin "1") (pinfunction "1_1") (pintype "passive"))
      (node (ref "IC1") (pin "M4") (pinfunction "DVDD_SXT_M4") (pintype "power_in"))
    )
    (net (code "21") (name "Net-(IC1F-VDD12O_VCO_SXT)") (class "Default")
      (node (ref "C80") (pin "2") (pinfunction "2_2") (pintype "passive"))
      (node (ref "FR8") (pin "1") (pinfunction "1_1") (pintype "passive"))
      (node (ref "IC1") (pin "J5") (pinfunction "VDD12O_VCO_SXT_J5") (pintype "power_in"))
      (node (ref "IC1") (pin "K6") (pinfunction "VDD12_VCO_SXT_K6") (pintype "power_in"))
    )
    (net (code "22") (name "Net-(IC1F-VDD12_LNA_RFE)") (class "Default")
      (node (ref "C77") (pin "1") (pinfunction "1_1") (pintype "passive"))
      (node (ref "FR12") (pin "1") (pinfunction "1_1") (pintype "passive"))
      (node (ref "IC1") (pin "AG5") (pinfunction "VDD12_LNA_RFE_AG5") (pintype "power_in"))
    )
    (net (code "23") (name "Net-(IC1F-VDD12_RXBUF)") (class "Default")
      (node (ref "C73") (pin "1") (pinfunction "1_1") (pintype "passive"))
      (node (ref "IC1") (pin "AP26") (pinfunction "VDD12_RXBUF_AP26") (pintype "power_in"))
      (node (ref "R67") (pin "1") (pinfunction "1_1") (pintype "passive"))
    )
    (net (code "24") (name "Net-(IC1F-VDD12_TIA_RFE)") (class "Default")
      (node (ref "C78") (pin "2") (pinfunction "2_2") (pintype "passive"))
      (node (ref "FR11") (pin "1") (pinfunction "1_1") (pintype "passive"))
      (node (ref "IC1") (pin "AD6") (pinfunction "VDD12_TIA_RFE_AD6") (pintype "power_in"))
    )
    (net (code "25") (name "Net-(IC1F-VDD12_TXBUF)") (class "Default")
      (node (ref "C65") (pin "1") (pinfunction "1_1") (pintype "passive"))
      (node (ref "IC1") (pin "G5") (pinfunction "VDD12_TXBUF_G5") (pintype "power_in"))
      (node (ref "R66") (pin "1") (pinfunction "1_1") (pintype "passive"))
    )
    (net (code "26") (name "Net-(IC1F-VDD12_VCO_SXR)") (class "Default")
      (node (ref "C74") (pin "1") (pinfunction "1_1") (pintype "passive"))
      (node (ref "FR15") (pin "1") (pinfunction "1_1") (pintype "passive"))
      (node (ref "IC1") (pin "AN23") (pinfunction "VDD12_VCO_SXR_AN23") (pintype "power_in"))
    )
    (net (code "27") (name "Net-(IC1F-VDD14_LNA_RFE)") (class "Default")
      (node (ref "C85") (pin "1") (pinfunction "1_1") (pintype "passive"))
      (node (ref "C86") (pin "1") (pinfunction "1_1") (pintype "passive"))
      (node (ref "C87") (pin "1") (pinfunction "1_1") (pintype "passive"))
      (node (ref "FR24") (pin "1") (pinfunction "1_1") (pintype "passive"))
      (node (ref "IC1") (pin "AD4") (pinfunction "VDD14_RBB_AD4") (pintype "power_in"))
      (node (ref "IC1") (pin "AF2") (pinfunction "VDD14_TIA_RFE_AF2") (pintype "power_in"))
      (node (ref "IC1") (pin "AF6") (pinfunction "VDD14_LNA_RFE_AF6") (pintype "power_in"))
    )
    (net (code "28") (name "Net-(IC1F-VDD14_VCO_CGEN)") (class "Default")
      (node (ref "C83") (pin "1") (pinfunction "1_1") (pintype "passive"))
      (node (ref "C84") (pin "1") (pinfunction "1_1") (pintype "passive"))
      (node (ref "FR25") (pin "1") (pinfunction "1_1") (pintype "passive"))
      (node (ref "IC1") (pin "C21") (pinfunction "VDD14_VCO_CGEN_C21") (pintype "power_in"))
    )
    (net (code "29") (name "Net-(IC1F-VDDO_DIV_SXT)") (class "Default")
      (node (ref "C82") (pin "1") (pinfunction "1_1") (pintype "passive"))
      (node (ref "FR22") (pin "1") (pinfunction "1_1") (pintype "passive"))
      (node (ref "IC1") (pin "K2") (pinfunction "VDDO_DIV_SXT_K2") (pintype "power_in"))
      (node (ref "IC1") (pin "L5") (pinfunction "VDD_DIV_SXT_L5") (pintype "power_in"))
    )
    (net (code "30") (name "Net-(IC1F-VDDO_TLOBUF_TRF)") (class "Default")
      (node (ref "C67") (pin "1") (pinfunction "1_1") (pintype "passive"))
      (node (ref "FR21") (pin "1") (pinfunction "1_1") (pintype "passive"))
      (node (ref "IC1") (pin "D6") (pinfunction "VDDO_TLOBUF_TRF_D6") (pintype "power_in"))
      (node (ref "IC1") (pin "F8") (pinfunction "VDD_TLOBUF_TRF_F8") (pintype "power_in"))
    )
    (net (code "31") (name "Net-(IC1F-VDD_AFE)") (class "Default")
      (node (ref "C72") (pin "1") (pinfunction "1_1") (pintype "passive"))
      (node (ref "FR17") (pin "1") (pinfunction "1_1") (pintype "passive"))
      (node (ref "IC1") (pin "AJ25") (pinfunction "VDD_AFE_AJ25") (pintype "power_in"))
    )
    (net (code "32") (name "Net-(IC1F-VDD_CP_CGEN)") (class "Default")
      (node (ref "C71") (pin "2") (pinfunction "2_2") (pintype "passive"))
      (node (ref "FR18") (pin "1") (pinfunction "1_1") (pintype "passive"))
      (node (ref "IC1") (pin "F20") (pinfunction "VDD_CP_CGEN_F20") (pintype "power_in"))
    )
    (net (code "33") (name "Net-(IC1F-VDD_CP_SXR)") (class "Default")
      (node (ref "C76") (pin "1") (pinfunction "1_1") (pintype "passive"))
      (node (ref "FR13") (pin "1") (pinfunction "1_1") (pintype "passive"))
      (node (ref "IC1") (pin "AL19") (pinfunction "VDD_CP_SXR_AL19") (pintype "power_in"))
    )
    (net (code "34") (name "Net-(IC1F-VDD_CP_SXT)") (class "Default")
      (node (ref "C79") (pin "1") (pinfunction "1_1") (pintype "passive"))
      (node (ref "FR9") (pin "1") (pinfunction "1_1") (pintype "passive"))
      (node (ref "IC1") (pin "J3") (pinfunction "VDD_CP_SXT_J3") (pintype "power_in"))
    )
    (net (code "35") (name "Net-(IC1F-VDD_DIV_CGEN)") (class "Default")
      (node (ref "C69") (pin "1") (pinfunction "1_1") (pintype "passive"))
      (node (ref "C70") (pin "1") (pinfunction "1_1") (pintype "passive"))
      (node (ref "FR19") (pin "1") (pinfunction "1_1") (pintype "passive"))
      (node (ref "IC1") (pin "E19") (pinfunction "VDD_DIV_CGEN_E19") (pintype "power_in"))
    )
    (net (code "36") (name "Net-(IC1F-VDD_DIV_SXR)") (class "Default")
      (node (ref "C75") (pin "1") (pinfunction "1_1") (pintype "passive"))
      (node (ref "FR14") (pin "1") (pinfunction "1_1") (pintype "passive"))
      (node (ref "IC1") (pin "AM20") (pinfunction "VDD_DIV_SXR_AM20") (pintype "power_in"))
    )
    (net (code "37") (name "Net-(IC1F-VDD_MXLOBUF_RFE)") (class "Default")
      (node (ref "C88") (pin "1") (pinfunction "1_1") (pintype "passive"))
      (node (ref "FR23") (pin "1") (pinfunction "1_1") (pintype "passive"))
      (node (ref "IC1") (pin "AN17") (pinfunction "VDD_MXLOBUF_RFE_AN17") (pintype "power_in"))
    )
    (net (code "38") (name "Net-(IC1F-VDD_TBB)") (class "Default")
      (node (ref "C66") (pin "1") (pinfunction "1_1") (pintype "passive"))
      (node (ref "FR1") (pin "1") (pinfunction "1_1") (pintype "passive"))
      (node (ref "FR10") (pin "1") (pinfunction "1_1") (pintype "passive"))
      (node (ref "IC1") (pin "P4") (pinfunction "VDD_TBB_P4") (pintype "power_in"))
    )
    (net (code "39") (name "Net-(IC1F-VDD_TPAD_TRF)") (class "Default")
      (node (ref "C68") (pin "1") (pinfunction "1_1") (pintype "passive"))
      (node (ref "FR20") (pin "1") (pinfunction "1_1") (pintype "passive"))
      (node (ref "IC1") (pin "B16") (pinfunction "VDD_TPAD_TRF_B16") (pintype "power_in"))
    )
    (net (code "40") (name "VCC1P4_LMS") (class "Default")
      (node (ref "FR10") (pin "2") (pinfunction "2_2") (pintype "passive"))
      (node (ref "FR22") (pin "2") (pinfunction "2_2") (pintype "passive"))
      (node (ref "FR23") (pin "2") (pinfunction "2_2") (pintype "passive"))
      (node (ref "FR24") (pin "2") (pinfunction "2_2") (pintype "passive"))
      (node (ref "FR25") (pin "2") (pinfunction "2_2") (pintype "passive"))
    )
    (net (code "41") (name "VCC1P8_LMS") (class "Default")
      (node (ref "FR26") (pin "2") (pinfunction "2_2") (pintype "passive"))
      (node (ref "FR27") (pin "1") (pinfunction "1_1") (pintype "passive"))
      (node (ref "FR28") (pin "1") (pinfunction "1_1") (pintype "passive"))
      (node (ref "FR29") (pin "2") (pinfunction "2_2") (pintype "passive"))
      (node (ref "FR30") (pin "2") (pinfunction "2_2") (pintype "passive"))
      (node (ref "FR31") (pin "2") (pinfunction "2_2") (pintype "passive"))
      (node (ref "FR32") (pin "2") (pinfunction "2_2") (pintype "passive"))
      (node (ref "FR33") (pin "2") (pinfunction "2_2") (pintype "passive"))
      (node (ref "R68") (pin "2") (pinfunction "2_2") (pintype "passive"))
      (node (ref "R70") (pin "2") (pinfunction "2_2") (pintype "passive"))
      (node (ref "R71") (pin "1") (pinfunction "1_1") (pintype "passive"))
    )
    (net (code "42") (name "VCC1P25_LMS") (class "Default")
      (node (ref "FR1") (pin "2") (pinfunction "2_2") (pintype "passive"))
      (node (ref "FR11") (pin "2") (pinfunction "2_2") (pintype "passive"))
      (node (ref "FR12") (pin "2") (pinfunction "2_2") (pintype "passive"))
      (node (ref "FR13") (pin "2") (pinfunction "2_2") (pintype "passive"))
      (node (ref "FR14") (pin "2") (pinfunction "2_2") (pintype "passive"))
      (node (ref "FR15") (pin "2") (pinfunction "2_2") (pintype "passive"))
      (node (ref "FR16") (pin "2") (pinfunction "2_2") (pintype "passive"))
      (node (ref "FR17") (pin "2") (pinfunction "2_2") (pintype "passive"))
      (node (ref "FR18") (pin "2") (pinfunction "2_2") (pintype "passive"))
      (node (ref "FR19") (pin "2") (pinfunction "2_2") (pintype "passive"))
      (node (ref "FR20") (pin "2") (pinfunction "2_2") (pintype "passive"))
      (node (ref "FR21") (pin "2") (pinfunction "2_2") (pintype "passive"))
      (node (ref "FR5") (pin "2") (pinfunction "2_2") (pintype "passive"))
      (node (ref "FR6") (pin "2") (pinfunction "2_2") (pintype "passive"))
      (node (ref "FR7") (pin "2") (pinfunction "2_2") (pintype "passive"))
      (node (ref "FR8") (pin "2") (pinfunction "2_2") (pintype "passive"))
      (node (ref "FR9") (pin "2") (pinfunction "2_2") (pintype "passive"))
      (node (ref "R65") (pin "1") (pinfunction "1_1") (pintype "passive"))
    )
    (net (code "43") (name "VDIO_LMS") (class "Default")
      (node (ref "R69") (pin "1") (pinfunction "1_1") (pintype "passive"))
    )
  )
)
